# capbot.net
KiCad netlist of a schematic drawn in EAGLE
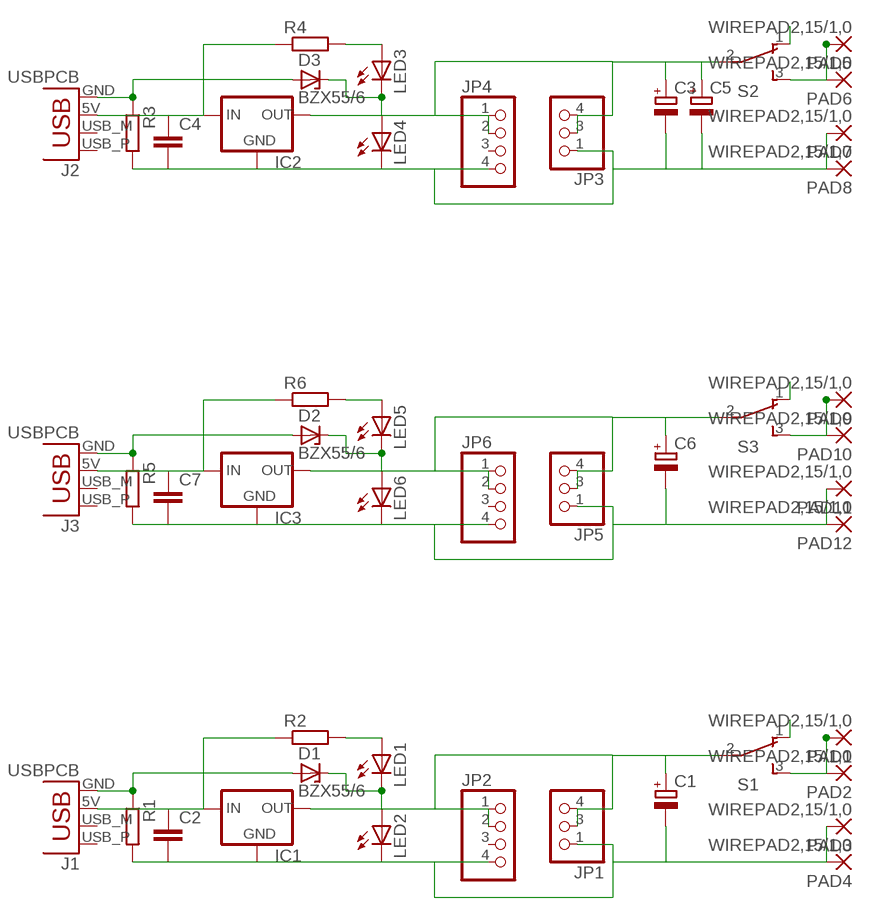
[diagram p0: schematic, sheet 1]

(export (version "E")
  (design (tool "Eeschema 10.0.6"))
  (components
    (comp (ref "C1")
      (value "CPOL-EUE5-10.5")
      (footprint "eagle-import:E5-10,5")
      (libsource (lib "eagle-import") (part "CPOL-EUE5-10.5"))
    )
    (comp (ref "C2")
      (value "C-EUC1206")
      (footprint "eagle-import:C1206")
      (libsource (lib "eagle-import") (part "C-EUC1206"))
    )
    (comp (ref "C3")
      (value "CPOL-EUE5-10.5")
      (footprint "eagle-import:E5-10,5")
      (libsource (lib "eagle-import") (part "CPOL-EUE5-10.5"))
    )
    (comp (ref "C4")
      (value "C-EUC1206")
      (footprint "eagle-import:C1206")
      (libsource (lib "eagle-import") (part "C-EUC1206"))
    )
    (comp (ref "C5")
      (value "CPOL-EUE5-10.5")
      (footprint "eagle-import:E5-10,5")
      (libsource (lib "eagle-import") (part "CPOL-EUE5-10.5"))
    )
    (comp (ref "C6")
      (value "CPOL-EUE5-10.5")
      (footprint "eagle-import:E5-10,5")
      (libsource (lib "eagle-import") (part "CPOL-EUE5-10.5"))
    )
    (comp (ref "C7")
      (value "C-EUC1206")
      (footprint "eagle-import:C1206")
      (libsource (lib "eagle-import") (part "C-EUC1206"))
    )
    (comp (ref "D1")
      (value "BZX55/6")
      (footprint "eagle-import:DO35Z6")
      (libsource (lib "eagle-import") (part "BZX55/6"))
    )
    (comp (ref "D2")
      (value "BZX55/6")
      (footprint "eagle-import:DO35Z6")
      (libsource (lib "eagle-import") (part "BZX55/6"))
    )
    (comp (ref "D3")
      (value "BZX55/6")
      (footprint "eagle-import:DO35Z6")
      (libsource (lib "eagle-import") (part "BZX55/6"))
    )
    (comp (ref "IC1")
      (value "MCP1700INLINE")
      (footprint "eagle-import:TO92-INLINE")
      (libsource (lib "eagle-import") (part "MCP1700INLINE"))
    )
    (comp (ref "IC2")
      (value "MCP1700INLINE")
      (footprint "eagle-import:TO92-INLINE")
      (libsource (lib "eagle-import") (part "MCP1700INLINE"))
    )
    (comp (ref "IC3")
      (value "MCP1700INLINE")
      (footprint "eagle-import:TO92-INLINE")
      (libsource (lib "eagle-import") (part "MCP1700INLINE"))
    )
    (comp (ref "J1")
      (value "USBPCB")
      (footprint "eagle-import:USB-A-PCB")
      (libsource (lib "eagle-import") (part "USBPCB"))
    )
    (comp (ref "J2")
      (value "USBPCB")
      (footprint "eagle-import:USB-A-PCB")
      (libsource (lib "eagle-import") (part "USBPCB"))
    )
    (comp (ref "J3")
      (value "USBPCB")
      (footprint "eagle-import:USB-A-PCB")
      (libsource (lib "eagle-import") (part "USBPCB"))
    )
    (comp (ref "JP1")
      (value "PINHD-1X3-4GAP")
      (footprint "eagle-import:1X04_GAP2")
      (libsource (lib "eagle-import") (part "PINHD-1X3-4GAP"))
    )
    (comp (ref "JP2")
      (value "PINHD-1X4")
      (footprint "eagle-import:1X04_OFFSETDOWN")
      (libsource (lib "eagle-import") (part "PINHD-1X4"))
    )
    (comp (ref "JP3")
      (value "PINHD-1X3-4GAP")
      (footprint "eagle-import:1X04_GAP2")
      (libsource (lib "eagle-import") (part "PINHD-1X3-4GAP"))
    )
    (comp (ref "JP4")
      (value "PINHD-1X4")
      (footprint "eagle-import:1X04_OFFSETDOWN")
      (libsource (lib "eagle-import") (part "PINHD-1X4"))
    )
    (comp (ref "JP5")
      (value "PINHD-1X3-4GAP")
      (footprint "eagle-import:1X04_GAP2")
      (libsource (lib "eagle-import") (part "PINHD-1X3-4GAP"))
    )
    (comp (ref "JP6")
      (value "PINHD-1X4")
      (footprint "eagle-import:1X04_OFFSETDOWN")
      (libsource (lib "eagle-import") (part "PINHD-1X4"))
    )
    (comp (ref "LED1")
      (value "LED3MM-MOREFLAT")
      (footprint "eagle-import:LED3MM-MOREFLAT")
      (libsource (lib "eagle-import") (part "LED3MM-MOREFLAT"))
    )
    (comp (ref "LED2")
      (value "LED3MM-MOREFLAT")
      (footprint "eagle-import:LED3MM-MOREFLAT")
      (libsource (lib "eagle-import") (part "LED3MM-MOREFLAT"))
    )
    (comp (ref "LED3")
      (value "LED3MM-MOREFLAT")
      (footprint "eagle-import:LED3MM-MOREFLAT")
      (libsource (lib "eagle-import") (part "LED3MM-MOREFLAT"))
    )
    (comp (ref "LED4")
      (value "LED3MM-MOREFLAT")
      (footprint "eagle-import:LED3MM-MOREFLAT")
      (libsource (lib "eagle-import") (part "LED3MM-MOREFLAT"))
    )
    (comp (ref "LED5")
      (value "LED3MM-MOREFLAT")
      (footprint "eagle-import:LED3MM-MOREFLAT")
      (libsource (lib "eagle-import") (part "LED3MM-MOREFLAT"))
    )
    (comp (ref "LED6")
      (value "LED3MM-MOREFLAT")
      (footprint "eagle-import:LED3MM-MOREFLAT")
      (libsource (lib "eagle-import") (part "LED3MM-MOREFLAT"))
    )
    (comp (ref "PAD1")
      (value "WIREPAD2,15/1,0")
      (footprint "eagle-import:2,15_1,0")
      (libsource (lib "eagle-import") (part "WIREPAD2,15/1,0"))
    )
    (comp (ref "PAD2")
      (value "WIREPAD2,15/1,0")
      (footprint "eagle-import:2,15_1,0")
      (libsource (lib "eagle-import") (part "WIREPAD2,15/1,0"))
    )
    (comp (ref "PAD3")
      (value "WIREPAD2,15/1,0")
      (footprint "eagle-import:2,15_1,0")
      (libsource (lib "eagle-import") (part "WIREPAD2,15/1,0"))
    )
    (comp (ref "PAD4")
      (value "WIREPAD2,15/1,0")
      (footprint "eagle-import:2,15_1,0")
      (libsource (lib "eagle-import") (part "WIREPAD2,15/1,0"))
    )
    (comp (ref "PAD5")
      (value "WIREPAD2,15/1,0")
      (footprint "eagle-import:2,15_1,0")
      (libsource (lib "eagle-import") (part "WIREPAD2,15/1,0"))
    )
    (comp (ref "PAD6")
      (value "WIREPAD2,15/1,0")
      (footprint "eagle-import:2,15_1,0")
      (libsource (lib "eagle-import") (part "WIREPAD2,15/1,0"))
    )
    (comp (ref "PAD7")
      (value "WIREPAD2,15/1,0")
      (footprint "eagle-import:2,15_1,0")
      (libsource (lib "eagle-import") (part "WIREPAD2,15/1,0"))
    )
    (comp (ref "PAD8")
      (value "WIREPAD2,15/1,0")
      (footprint "eagle-import:2,15_1,0")
      (libsource (lib "eagle-import") (part "WIREPAD2,15/1,0"))
    )
    (comp (ref "PAD9")
      (value "WIREPAD2,15/1,0")
      (footprint "eagle-import:2,15_1,0")
      (libsource (lib "eagle-import") (part "WIREPAD2,15/1,0"))
    )
    (comp (ref "PAD10")
      (value "WIREPAD2,15/1,0")
      (footprint "eagle-import:2,15_1,0")
      (libsource (lib "eagle-import") (part "WIREPAD2,15/1,0"))
    )
    (comp (ref "PAD11")
      (value "WIREPAD2,15/1,0")
      (footprint "eagle-import:2,15_1,0")
      (libsource (lib "eagle-import") (part "WIREPAD2,15/1,0"))
    )
    (comp (ref "PAD12")
      (value "WIREPAD2,15/1,0")
      (footprint "eagle-import:2,15_1,0")
      (libsource (lib "eagle-import") (part "WIREPAD2,15/1,0"))
    )
    (comp (ref "R1")
      (value "R-EU_0207/7")
      (footprint "eagle-import:0207_7")
      (libsource (lib "eagle-import") (part "R-EU_0207/7"))
    )
    (comp (ref "R2")
      (value "R-EU_0207/7")
      (footprint "eagle-import:0207_7")
      (libsource (lib "eagle-import") (part "R-EU_0207/7"))
    )
    (comp (ref "R3")
      (value "R-EU_0207/7")
      (footprint "eagle-import:0207_7")
      (libsource (lib "eagle-import") (part "R-EU_0207/7"))
    )
    (comp (ref "R4")
      (value "R-EU_0207/7")
      (footprint "eagle-import:0207_7")
      (libsource (lib "eagle-import") (part "R-EU_0207/7"))
    )
    (comp (ref "R5")
      (value "R-EU_0207/7")
      (footprint "eagle-import:0207_7")
      (libsource (lib "eagle-import") (part "R-EU_0207/7"))
    )
    (comp (ref "R6")
      (value "R-EU_0207/7")
      (footprint "eagle-import:0207_7")
      (libsource (lib "eagle-import") (part "R-EU_0207/7"))
    )
    (comp (ref "S1")
      (value "TL36PO")
      (footprint "eagle-import:TL3XPO")
      (libsource (lib "eagle-import") (part "TL36PO"))
    )
    (comp (ref "S2")
      (value "TL36PO")
      (footprint "eagle-import:TL3XPO")
      (libsource (lib "eagle-import") (part "TL36PO"))
    )
    (comp (ref "S3")
      (value "TL36PO")
      (footprint "eagle-import:TL3XPO")
      (libsource (lib "eagle-import") (part "TL36PO"))
    )
  )
  (nets
    (net (code "1") (name "Net-(D1-PadA)") (class "Default")
      (node (ref "D1") (pin "A") (pinfunction "A_A") (pintype "passive"))
      (node (ref "J1") (pin "GND") (pinfunction "GND_GND") (pintype "bidirectional"))
      (node (ref "R1") (pin "1") (pinfunction "1_1") (pintype "passive"))
    )
    (net (code "2") (name "Net-(D2-PadA)") (class "Default")
      (node (ref "D2") (pin "A") (pinfunction "A_A") (pintype "passive"))
      (node (ref "J3") (pin "GND") (pinfunction "GND_GND") (pintype "bidirectional"))
      (node (ref "R5") (pin "1") (pinfunction "1_1") (pintype "passive"))
    )
    (net (code "3") (name "Net-(D3-PadA)") (class "Default")
      (node (ref "D3") (pin "A") (pinfunction "A_A") (pintype "passive"))
      (node (ref "J2") (pin "GND") (pinfunction "GND_GND") (pintype "bidirectional"))
      (node (ref "R3") (pin "1") (pinfunction "1_1") (pintype "passive"))
    )
    (net (code "4") (name "Net-(IC1-GND)") (class "Default")
      (node (ref "C1") (pin "-") (pinfunction "-_-") (pintype "passive"))
      (node (ref "C2") (pin "2") (pinfunction "2_2") (pintype "passive"))
      (node (ref "IC1") (pin "1") (pinfunction "GND_1") (pintype "input"))
      (node (ref "JP1") (pin "1") (pinfunction "1_1") (pintype "passive"))
      (node (ref "JP2") (pin "4") (pinfunction "4_4") (pintype "passive"))
      (node (ref "LED2") (pin "K") (pinfunction "C_K") (pintype "passive"))
      (node (ref "PAD3") (pin "1") (pinfunction "P_1") (pintype "passive"))
      (node (ref "PAD4") (pin "1") (pinfunction "P_1") (pintype "passive"))
      (node (ref "R1") (pin "2") (pinfunction "2_2") (pintype "passive"))
    )
    (net (code "5") (name "Net-(IC1-IN)") (class "Default")
      (node (ref "C2") (pin "1") (pinfunction "1_1") (pintype "passive"))
      (node (ref "IC1") (pin "2") (pinfunction "IN_2") (pintype "input"))
      (node (ref "J1") (pin "5V") (pinfunction "VBUS_5V") (pintype "bidirectional"))
      (node (ref "R2") (pin "1") (pinfunction "1_1") (pintype "passive"))
    )
    (net (code "6") (name "Net-(IC1-OUT)") (class "Default")
      (node (ref "C1") (pin "+") (pinfunction "+_+") (pintype "passive"))
      (node (ref "IC1") (pin "3") (pinfunction "OUT_3") (pintype "passive"))
      (node (ref "JP1") (pin "3") (pinfunction "2_3") (pintype "passive"))
      (node (ref "JP1") (pin "4") (pinfunction "3_4") (pintype "passive"))
      (node (ref "JP2") (pin "1") (pinfunction "1_1") (pintype "passive"))
      (node (ref "JP2") (pin "2") (pinfunction "2_2") (pintype "passive"))
      (node (ref "S1") (pin "2") (pinfunction "P_2") (pintype "passive"))
    )
    (net (code "7") (name "Net-(IC2-GND)") (class "Default")
      (node (ref "C3") (pin "-") (pinfunction "-_-") (pintype "passive"))
      (node (ref "C4") (pin "2") (pinfunction "2_2") (pintype "passive"))
      (node (ref "C5") (pin "-") (pinfunction "-_-") (pintype "passive"))
      (node (ref "IC2") (pin "1") (pinfunction "GND_1") (pintype "input"))
      (node (ref "JP3") (pin "1") (pinfunction "1_1") (pintype "passive"))
      (node (ref "JP4") (pin "4") (pinfunction "4_4") (pintype "passive"))
      (node (ref "LED4") (pin "K") (pinfunction "C_K") (pintype "passive"))
      (node (ref "PAD7") (pin "1") (pinfunction "P_1") (pintype "passive"))
      (node (ref "PAD8") (pin "1") (pinfunction "P_1") (pintype "passive"))
      (node (ref "R3") (pin "2") (pinfunction "2_2") (pintype "passive"))
    )
    (net (code "8") (name "Net-(IC2-IN)") (class "Default")
      (node (ref "C4") (pin "1") (pinfunction "1_1") (pintype "passive"))
      (node (ref "IC2") (pin "2") (pinfunction "IN_2") (pintype "input"))
      (node (ref "J2") (pin "5V") (pinfunction "VBUS_5V") (pintype "bidirectional"))
      (node (ref "R4") (pin "1") (pinfunction "1_1") (pintype "passive"))
    )
    (net (code "9") (name "Net-(IC2-OUT)") (class "Default")
      (node (ref "C3") (pin "+") (pinfunction "+_+") (pintype "passive"))
      (node (ref "C5") (pin "+") (pinfunction "+_+") (pintype "passive"))
      (node (ref "IC2") (pin "3") (pinfunction "OUT_3") (pintype "passive"))
      (node (ref "JP3") (pin "3") (pinfunction "2_3") (pintype "passive"))
      (node (ref "JP3") (pin "4") (pinfunction "3_4") (pintype "passive"))
      (node (ref "JP4") (pin "1") (pinfunction "1_1") (pintype "passive"))
      (node (ref "JP4") (pin "2") (pinfunction "2_2") (pintype "passive"))
      (node (ref "S2") (pin "2") (pinfunction "P_2") (pintype "passive"))
    )
    (net (code "10") (name "Net-(IC3-GND)") (class "Default")
      (node (ref "C6") (pin "-") (pinfunction "-_-") (pintype "passive"))
      (node (ref "C7") (pin "2") (pinfunction "2_2") (pintype "passive"))
      (node (ref "IC3") (pin "1") (pinfunction "GND_1") (pintype "input"))
      (node (ref "JP5") (pin "1") (pinfunction "1_1") (pintype "passive"))
      (node (ref "JP6") (pin "4") (pinfunction "4_4") (pintype "passive"))
      (node (ref "LED6") (pin "K") (pinfunction "C_K") (pintype "passive"))
      (node (ref "PAD11") (pin "1") (pinfunction "P_1") (pintype "passive"))
      (node (ref "PAD12") (pin "1") (pinfunction "P_1") (pintype "passive"))
      (node (ref "R5") (pin "2") (pinfunction "2_2") (pintype "passive"))
    )
    (net (code "11") (name "Net-(IC3-IN)") (class "Default")
      (node (ref "C7") (pin "1") (pinfunction "1_1") (pintype "passive"))
      (node (ref "IC3") (pin "2") (pinfunction "IN_2") (pintype "input"))
      (node (ref "J3") (pin "5V") (pinfunction "VBUS_5V") (pintype "bidirectional"))
      (node (ref "R6") (pin "1") (pinfunction "1_1") (pintype "passive"))
    )
    (net (code "12") (name "Net-(IC3-OUT)") (class "Default")
      (node (ref "C6") (pin "+") (pinfunction "+_+") (pintype "passive"))
      (node (ref "IC3") (pin "3") (pinfunction "OUT_3") (pintype "passive"))
      (node (ref "JP5") (pin "3") (pinfunction "2_3") (pintype "passive"))
      (node (ref "JP5") (pin "4") (pinfunction "3_4") (pintype "passive"))
      (node (ref "JP6") (pin "1") (pinfunction "1_1") (pintype "passive"))
      (node (ref "JP6") (pin "2") (pinfunction "2_2") (pintype "passive"))
      (node (ref "S3") (pin "2") (pinfunction "P_2") (pintype "passive"))
    )
    (net (code "13") (name "Net-(LED1-C)") (class "Default")
      (node (ref "D1") (pin "C") (pinfunction "C_C") (pintype "passive"))
      (node (ref "LED1") (pin "K") (pinfunction "C_K") (pintype "passive"))
      (node (ref "LED2") (pin "A") (pinfunction "A_A") (pintype "passive"))
    )
    (net (code "14") (name "Net-(LED1-PadA)") (class "Default")
      (node (ref "LED1") (pin "A") (pinfunction "A_A") (pintype "passive"))
      (node (ref "R2") (pin "2") (pinfunction "2_2") (pintype "passive"))
    )
    (net (code "15") (name "Net-(LED3-C)") (class "Default")
      (node (ref "D3") (pin "C") (pinfunction "C_C") (pintype "passive"))
      (node (ref "LED3") (pin "K") (pinfunction "C_K") (pintype "passive"))
      (node (ref "LED4") (pin "A") (pinfunction "A_A") (pintype "passive"))
    )
    (net (code "16") (name "Net-(LED3-PadA)") (class "Default")
      (node (ref "LED3") (pin "A") (pinfunction "A_A") (pintype "passive"))
      (node (ref "R4") (pin "2") (pinfunction "2_2") (pintype "passive"))
    )
    (net (code "17") (name "Net-(LED5-C)") (class "Default")
      (node (ref "D2") (pin "C") (pinfunction "C_C") (pintype "passive"))
      (node (ref "LED5") (pin "K") (pinfunction "C_K") (pintype "passive"))
      (node (ref "LED6") (pin "A") (pinfunction "A_A") (pintype "passive"))
    )
    (net (code "18") (name "Net-(LED5-PadA)") (class "Default")
      (node (ref "LED5") (pin "A") (pinfunction "A_A") (pintype "passive"))
      (node (ref "R6") (pin "2") (pinfunction "2_2") (pintype "passive"))
    )
    (net (code "19") (name "Net-(PAD1-P)") (class "Default")
      (node (ref "PAD1") (pin "1") (pinfunction "P_1") (pintype "passive"))
      (node (ref "PAD2") (pin "1") (pinfunction "P_1") (pintype "passive"))
      (node (ref "S1") (pin "3") (pinfunction "S_3") (pintype "passive"))
    )
    (net (code "20") (name "Net-(PAD5-P)") (class "Default")
      (node (ref "PAD5") (pin "1") (pinfunction "P_1") (pintype "passive"))
      (node (ref "PAD6") (pin "1") (pinfunction "P_1") (pintype "passive"))
      (node (ref "S2") (pin "3") (pinfunction "S_3") (pintype "passive"))
    )
    (net (code "21") (name "Net-(PAD10-P)") (class "Default")
      (node (ref "PAD10") (pin "1") (pinfunction "P_1") (pintype "passive"))
      (node (ref "PAD9") (pin "1") (pinfunction "P_1") (pintype "passive"))
      (node (ref "S3") (pin "3") (pinfunction "S_3") (pintype "passive"))
    )
    (net (code "22") (name "unconnected-(J1-D+-PadUSB_P)") (class "Default")
      (node (ref "J1") (pin "USB_P") (pinfunction "D+_USB_P") (pintype "bidirectional"))
    )
    (net (code "23") (name "unconnected-(J1-D--PadUSB_M)") (class "Default")
      (node (ref "J1") (pin "USB_M") (pinfunction "D-_USB_M") (pintype "bidirectional"))
    )
    (net (code "24") (name "unconnected-(J2-D+-PadUSB_P)") (class "Default")
      (node (ref "J2") (pin "USB_P") (pinfunction "D+_USB_P") (pintype "bidirectional"))
    )
    (net (code "25") (name "unconnected-(J2-D--PadUSB_M)") (class "Default")
      (node (ref "J2") (pin "USB_M") (pinfunction "D-_USB_M") (pintype "bidirectional"))
    )
    (net (code "26") (name "unconnected-(J3-D+-PadUSB_P)") (class "Default")
      (node (ref "J3") (pin "USB_P") (pinfunction "D+_USB_P") (pintype "bidirectional"))
    )
    (net (code "27") (name "unconnected-(J3-D--PadUSB_M)") (class "Default")
      (node (ref "J3") (pin "USB_M") (pinfunction "D-_USB_M") (pintype "bidirectional"))
    )
    (net (code "28") (name "unconnected-(JP2-Pad3)") (class "Default")
      (node (ref "JP2") (pin "3") (pinfunction "3_3") (pintype "passive"))
    )
    (net (code "29") (name "unconnected-(JP4-Pad3)") (class "Default")
      (node (ref "JP4") (pin "3") (pinfunction "3_3") (pintype "passive"))
    )
    (net (code "30") (name "unconnected-(JP6-Pad3)") (class "Default")
      (node (ref "JP6") (pin "3") (pinfunction "3_3") (pintype "passive"))
    )
    (net (code "31") (name "unconnected-(S1-O-Pad1)") (class "Default")
      (node (ref "S1") (pin "1") (pinfunction "O_1") (pintype "passive"))
    )
    (net (code "32") (name "unconnected-(S2-O-Pad1)") (class "Default")
      (node (ref "S2") (pin "1") (pinfunction "O_1") (pintype "passive"))
    )
    (net (code "33") (name "unconnected-(S3-O-Pad1)") (class "Default")
      (node (ref "S3") (pin "1") (pinfunction "O_1") (pintype "passive"))
    )
  )
)
